# SENSOR.net
KiCad netlist of a schematic drawn in Altium Designer
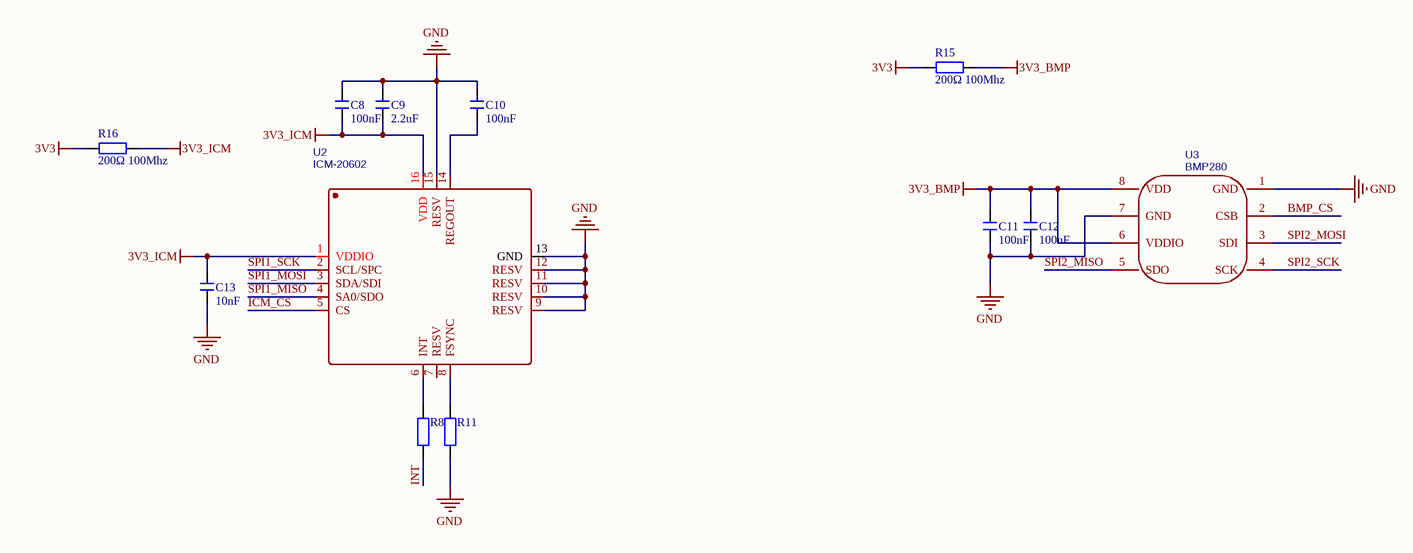
[diagram p0: SENSOR.SchDoc]

(export (version "E")
  (design (tool "Eeschema 10.0.6"))
  (components
    (comp (ref "C8")
      (value "100nF")
      (footprint "C 0603_L")
      (description "无极性贴片电容")
      (fields (field (name "版权归属") "源创客"))
      (libsource (lib "3.1   - 电阻-电容-电感") (part "C"))
    )
    (comp (ref "C9")
      (value "2.2uF")
      (footprint "C 0603_L")
      (description "无极性贴片电容")
      (fields (field (name "版权归属") "源创客"))
      (libsource (lib "3.1   - 电阻-电容-电感") (part "C"))
    )
    (comp (ref "C10")
      (value "100nF")
      (footprint "C 0603_L")
      (description "无极性贴片电容")
      (fields (field (name "版权归属") "源创客"))
      (libsource (lib "3.1   - 电阻-电容-电感") (part "C"))
    )
    (comp (ref "C11")
      (value "100nF")
      (footprint "C 0603_L")
      (description "无极性贴片电容")
      (fields (field (name "版权归属") "源创客"))
      (libsource (lib "3.1   - 电阻-电容-电感") (part "C"))
    )
    (comp (ref "C12")
      (value "100nF")
      (footprint "C 0603_L")
      (description "无极性贴片电容")
      (fields (field (name "版权归属") "源创客"))
      (libsource (lib "3.1   - 电阻-电容-电感") (part "C"))
    )
    (comp (ref "C13")
      (value "10nF")
      (footprint "C 0603_L")
      (description "无极性贴片电容")
      (fields (field (name "版权归属") "源创客"))
      (libsource (lib "3.1   - 电阻-电容-电感") (part "C"))
    )
    (comp (ref "R8")
      (value "~")
      (footprint "R 0603_L")
      (description "贴片电阻")
      (fields (field (name "版权归属") "源创客"))
      (libsource (lib "3.1   - 电阻-电容-电感") (part "R"))
    )
    (comp (ref "R11")
      (value "~")
      (footprint "R 0603_L")
      (description "贴片电阻")
      (fields (field (name "版权归属") "源创客"))
      (libsource (lib "3.1   - 电阻-电容-电感") (part "R"))
    )
    (comp (ref "R15")
      (value "200Ω 100Mhz")
      (footprint "R 0805_L")
      (description "磁珠")
      (fields (field (name "版权归属") "源创客"))
      (libsource (lib "3.1   - 电阻-电容-电感") (part "R"))
    )
    (comp (ref "R16")
      (value "200Ω 100Mhz")
      (footprint "R 0805_L")
      (description "磁珠")
      (fields (field (name "版权归属") "源创客"))
      (libsource (lib "3.1   - 电阻-电容-电感") (part "R"))
    )
    (comp (ref "U2")
      (value "ICM-20602")
      (footprint "LGA-16_L3.0-W3.0-P0.50-BL")
      (description "六轴MEMS运动跟踪设备")
      (fields (field (name "MANUFACTURER") "TDK InvenSense(应美盛)") (field (name "CONTRIBUTOR") "LCSC"))
      (libsource (lib "altium-import") (part "root_0_ICM-20602_"))
    )
    (comp (ref "U3")
      (value "BMP280")
      (footprint "LGA-8_L2.5-W2.0-P0.65_AMP6127")
      (fields (field (name "MANUFACTURER") "Bosch(博世)"))
      (libsource (lib "altium-import") (part "root_0_BMP280_"))
    )
  )
  (nets
    (net (code "1") (name "/BMP_CS") (class "Default")
      (node (ref "U3") (pin "2") (pinfunction "CSB_2") (pintype "passive"))
    )
    (net (code "2") (name "/ICM_CS") (class "Default")
      (node (ref "U2") (pin "5") (pinfunction "CS_5") (pintype "passive"))
    )
    (net (code "3") (name "/INT") (class "Default")
      (node (ref "R8") (pin "2") (pinfunction "2_2") (pintype "passive"))
    )
    (net (code "4") (name "/SPI1_MISO") (class "Default")
      (node (ref "U2") (pin "4") (pinfunction "SA0/SDO_4") (pintype "passive"))
    )
    (net (code "5") (name "/SPI1_MOSI") (class "Default")
      (node (ref "U2") (pin "3") (pinfunction "SDA/SDI_3") (pintype "passive"))
    )
    (net (code "6") (name "/SPI1_SCK") (class "Default")
      (node (ref "U2") (pin "2") (pinfunction "SCL/SPC_2") (pintype "passive"))
    )
    (net (code "7") (name "/SPI2_MISO") (class "Default")
      (node (ref "U3") (pin "5") (pinfunction "SDO_5") (pintype "passive"))
    )
    (net (code "8") (name "/SPI2_MOSI") (class "Default")
      (node (ref "U3") (pin "3") (pinfunction "SDI_3") (pintype "passive"))
    )
    (net (code "9") (name "/SPI2_SCK") (class "Default")
      (node (ref "U3") (pin "4") (pinfunction "SCK_4") (pintype "passive"))
    )
    (net (code "10") (name "3V3") (class "Default")
      (node (ref "R15") (pin "1") (pinfunction "1_1") (pintype "passive"))
      (node (ref "R16") (pin "1") (pinfunction "1_1") (pintype "passive"))
    )
    (net (code "11") (name "3V3_BMP") (class "Default")
      (node (ref "C11") (pin "1") (pinfunction "1_1") (pintype "passive"))
      (node (ref "C12") (pin "1") (pinfunction "1_1") (pintype "passive"))
      (node (ref "R15") (pin "2") (pinfunction "2_2") (pintype "passive"))
      (node (ref "U3") (pin "6") (pinfunction "VDDIO_6") (pintype "passive"))
      (node (ref "U3") (pin "8") (pinfunction "VDD_8") (pintype "passive"))
    )
    (net (code "12") (name "3V3_ICM") (class "Default")
      (node (ref "C13") (pin "2") (pinfunction "2_2") (pintype "passive"))
      (node (ref "C8") (pin "2") (pinfunction "2_2") (pintype "passive"))
      (node (ref "C9") (pin "2") (pinfunction "2_2") (pintype "passive"))
      (node (ref "R16") (pin "2") (pinfunction "2_2") (pintype "passive"))
      (node (ref "U2") (pin "1") (pinfunction "VDDIO_1") (pintype "passive"))
      (node (ref "U2") (pin "16") (pinfunction "VDD_16") (pintype "passive"))
    )
    (net (code "13") (name "GND") (class "Default")
      (node (ref "C10") (pin "1") (pinfunction "1_1") (pintype "passive"))
      (node (ref "C11") (pin "2") (pinfunction "2_2") (pintype "passive"))
      (node (ref "C12") (pin "2") (pinfunction "2_2") (pintype "passive"))
      (node (ref "C13") (pin "1") (pinfunction "1_1") (pintype "passive"))
      (node (ref "C8") (pin "1") (pinfunction "1_1") (pintype "passive"))
      (node (ref "C9") (pin "1") (pinfunction "1_1") (pintype "passive"))
      (node (ref "R11") (pin "2") (pinfunction "2_2") (pintype "passive"))
      (node (ref "U2") (pin "10") (pinfunction "RESV_10") (pintype "passive"))
      (node (ref "U2") (pin "11") (pinfunction "RESV_11") (pintype "passive"))
      (node (ref "U2") (pin "12") (pinfunction "RESV_12") (pintype "passive"))
      (node (ref "U2") (pin "13") (pinfunction "GND_13") (pintype "passive"))
      (node (ref "U2") (pin "15") (pinfunction "RESV_15") (pintype "passive"))
      (node (ref "U2") (pin "9") (pinfunction "RESV_9") (pintype "passive"))
      (node (ref "U3") (pin "1") (pinfunction "GND_1") (pintype "passive"))
      (node (ref "U3") (pin "7") (pinfunction "GND_7") (pintype "passive"))
    )
    (net (code "14") (name "Net-(U2-FSYNC)") (class "Default")
      (node (ref "R11") (pin "1") (pinfunction "1_1") (pintype "passive"))
      (node (ref "U2") (pin "8") (pinfunction "FSYNC_8") (pintype "passive"))
    )
    (net (code "15") (name "Net-(U2-INT)") (class "Default")
      (node (ref "R8") (pin "1") (pinfunction "1_1") (pintype "passive"))
      (node (ref "U2") (pin "6") (pinfunction "INT_6") (pintype "passive"))
    )
    (net (code "16") (name "Net-(U2-REGOUT)") (class "Default")
      (node (ref "C10") (pin "2") (pinfunction "2_2") (pintype "passive"))
      (node (ref "U2") (pin "14") (pinfunction "REGOUT_14") (pintype "passive"))
    )
    (net (code "17") (name "unconnected-(U2-RESV-Pad7)") (class "Default")
      (node (ref "U2") (pin "7") (pinfunction "RESV_7") (pintype "passive"))
    )
  )
)
